# Galka.net
KiCad netlist of a schematic drawn in EAGLE
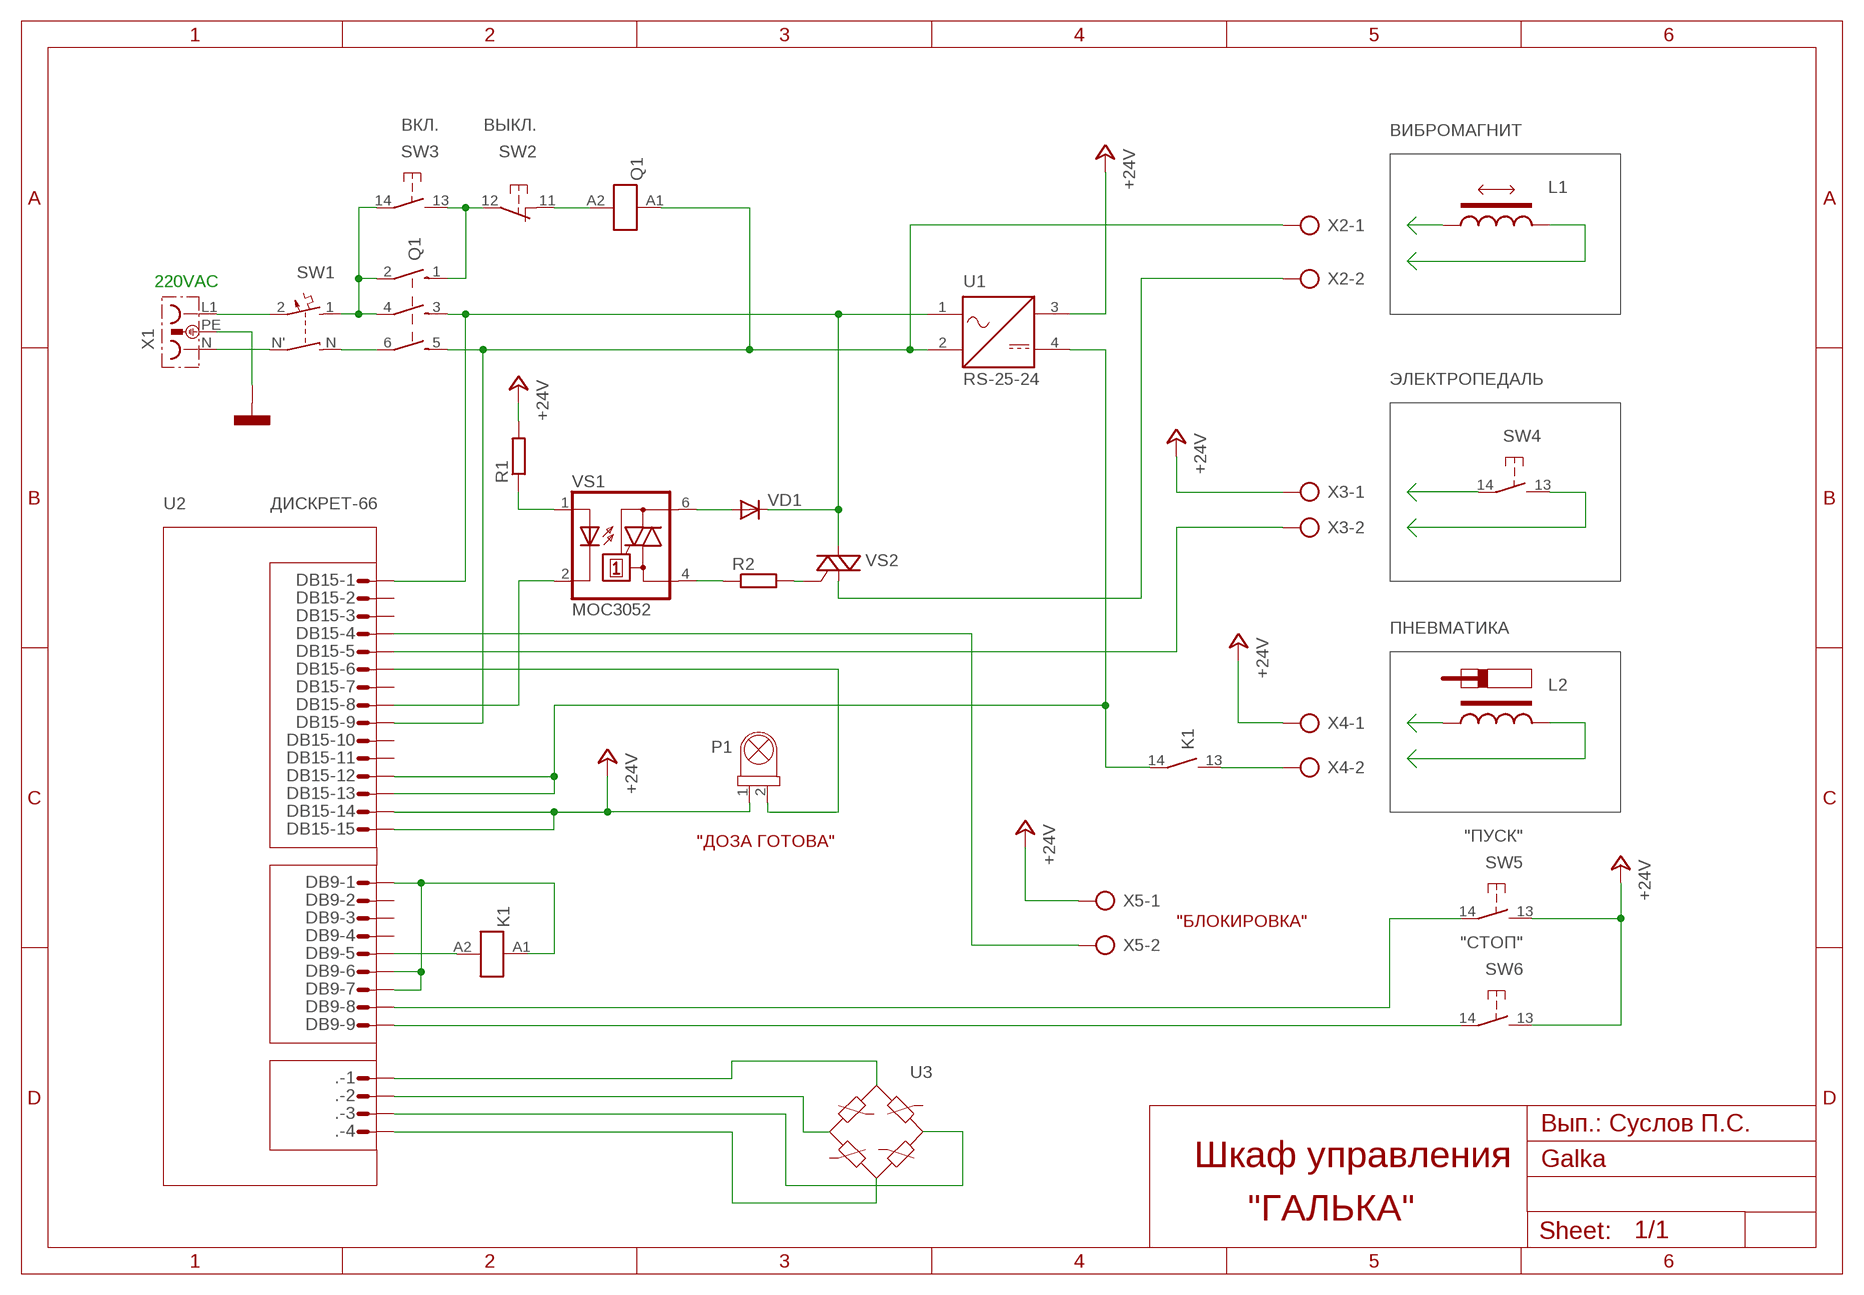
[diagram p0: schematic, sheet 1]

(export (version "E")
  (design (tool "Eeschema 10.0.6"))
  (components
    (comp (ref ".")
      (value "L04P")
      (footprint "eagle-import:L04P")
      (libsource (lib "eagle-import") (part "L04P"))
    )
    (comp (ref "DB9")
      (value "L09P")
      (footprint "eagle-import:L09P")
      (libsource (lib "eagle-import") (part "L09P"))
    )
    (comp (ref "DB15")
      (value "L15P")
      (footprint "eagle-import:L15P")
      (libsource (lib "eagle-import") (part "L15P"))
    )
    (comp (ref "K1")
      (value "HILFSSCHUETZ_13-14")
      (footprint "eagle-import:HILFSSCHUETZ_13-14")
      (libsource (lib "eagle-import") (part "HILFSSCHUETZ_13-14"))
    )
    (comp (ref "L1")
      (value "L-US0204/5")
      (footprint "eagle-import:0204_5")
      (libsource (lib "eagle-import") (part "L-US0204/5"))
    )
    (comp (ref "L2")
      (value "L-US0204/5")
      (footprint "eagle-import:0204_5")
      (libsource (lib "eagle-import") (part "L-US0204/5"))
    )
    (comp (ref "P1")
      (value "BLINK/BLITZLEUCHTE")
      (footprint "eagle-import:LAMPE")
      (libsource (lib "eagle-import") (part "BLINK/BLITZLEUCHTE"))
    )
    (comp (ref "Q1")
      (value "HAUPTSCHUETZ_3-POL")
      (footprint "eagle-import:HAUPTSCHUETZ_3-POL")
      (libsource (lib "eagle-import") (part "HAUPTSCHUETZ_3-POL"))
    )
    (comp (ref "R1")
      (value "R-EU_0204/2V")
      (footprint "eagle-import:0204V")
      (libsource (lib "eagle-import") (part "R-EU_0204/2V"))
    )
    (comp (ref "R2")
      (value "R-EU_0204/2V")
      (footprint "eagle-import:0204V")
      (libsource (lib "eagle-import") (part "R-EU_0204/2V"))
    )
    (comp (ref "SW1")
      (value "LEITUNGSSCHUTZSCHALTER_2-POL")
      (footprint "eagle-import:LEITUNGSSCHUTZSCHALTER_2-POL")
      (libsource (lib "eagle-import") (part "LEITUNGSSCHUTZSCHALTER_2-POL"))
    )
    (comp (ref "SW2")
      (value "ВЫКЛ.")
      (footprint "eagle-import:OEFFNER_TASTSCHALTER")
      (libsource (lib "eagle-import") (part "OEFFNER_TASTSCHALTER"))
    )
    (comp (ref "SW3")
      (value "ВКЛ.")
      (footprint "eagle-import:SCHLIESSER_TASTSCHALTER")
      (libsource (lib "eagle-import") (part "SCHLIESSER_TASTSCHALTER"))
    )
    (comp (ref "SW4")
      (value "SCHLIESSER_TASTSCHALTER")
      (footprint "eagle-import:SCHLIESSER_TASTSCHALTER")
      (libsource (lib "eagle-import") (part "SCHLIESSER_TASTSCHALTER"))
    )
    (comp (ref "SW5")
      (value "\"ПУСК\"")
      (footprint "eagle-import:SCHLIESSER_TASTSCHALTER")
      (libsource (lib "eagle-import") (part "SCHLIESSER_TASTSCHALTER"))
    )
    (comp (ref "SW6")
      (value "\"СТОП\"")
      (footprint "eagle-import:SCHLIESSER_TASTSCHALTER")
      (libsource (lib "eagle-import") (part "SCHLIESSER_TASTSCHALTER"))
    )
    (comp (ref "U1")
      (value "RS-25-24")
      (footprint "eagle-import:NETZTEIL_GLEICHSPANNUNG")
      (libsource (lib "eagle-import") (part "NETZTEIL_GLEICHSPANNUNG"))
    )
    (comp (ref "VD1")
      (value "1N4148DO35-7")
      (footprint "eagle-import:DO35-7")
      (libsource (lib "eagle-import") (part "1N4148DO35-7"))
    )
    (comp (ref "VS1")
      (value "MOC3052")
      (footprint "eagle-import:DIL06B")
      (libsource (lib "eagle-import") (part "MOC30T42"))
    )
    (comp (ref "VS2")
      (value "TRIAC")
      (footprint "eagle-import:TRIAC")
      (libsource (lib "eagle-import") (part "TRIAC"))
    )
    (comp (ref "X1")
      (value "STECKDOSE")
      (footprint "eagle-import:STECKDOSE")
      (libsource (lib "eagle-import") (part "STECKDOSE"))
    )
    (comp (ref "X2")
      (value "AK500/2")
      (footprint "eagle-import:AK500_2")
      (libsource (lib "eagle-import") (part "AK500/2"))
    )
    (comp (ref "X3")
      (value "AK500/2")
      (footprint "eagle-import:AK500_2")
      (libsource (lib "eagle-import") (part "AK500/2"))
    )
    (comp (ref "X4")
      (value "AK500/2")
      (footprint "eagle-import:AK500_2")
      (libsource (lib "eagle-import") (part "AK500/2"))
    )
    (comp (ref "X5")
      (value "AK500/2")
      (footprint "eagle-import:AK500_2")
      (libsource (lib "eagle-import") (part "AK500/2"))
    )
    (comp (ref "X6")
      (value "MASSE_ALLGEMEIN")
      (footprint "eagle-import:MASSE_ALLGEMEIN")
      (libsource (lib "eagle-import") (part "MASSE_ALLGEMEIN"))
    )
  )
  (nets
    (net (code "1") (name "+24V") (class "Default")
      (node (ref "DB15") (pin "14") (pinfunction "S_14") (pintype "passive"))
      (node (ref "DB15") (pin "15") (pinfunction "S_15") (pintype "passive"))
      (node (ref "P1") (pin "1") (pinfunction "X1_1") (pintype "passive"))
      (node (ref "R1") (pin "2") (pinfunction "2_2") (pintype "passive"))
      (node (ref "SW5") (pin "13") (pinfunction "3_13") (pintype "input"))
      (node (ref "SW6") (pin "13") (pinfunction "3_13") (pintype "input"))
      (node (ref "U1") (pin "3") (pinfunction "3_3") (pintype "passive"))
      (node (ref "X3") (pin "1") (pinfunction "KL_1") (pintype "passive"))
      (node (ref "X4") (pin "1") (pinfunction "KL_1") (pintype "passive"))
      (node (ref "X5") (pin "1") (pinfunction "KL_1") (pintype "passive"))
    )
    (net (code "2") (name "/SW1") (class "Default")
      (node (ref "DB15") (pin "1") (pinfunction "S_1") (pintype "passive"))
      (node (ref "Q1") (pin "3") (pinfunction "3_3") (pintype "passive"))
      (node (ref "SW1") (pin "2") (pinfunction "2_2") (pintype "passive"))
      (node (ref "U1") (pin "1") (pinfunction "1_1") (pintype "passive"))
      (node (ref "VD1") (pin "C") (pinfunction "C_C") (pintype "passive"))
      (node (ref "VS2") (pin "A1") (pinfunction "A1_A1") (pintype "passive"))
      (node (ref "X1") (pin "L1") (pinfunction "L1_L1") (pintype "passive"))
    )
    (net (code "3") (name "Net-(DB9A-S)") (class "Default")
      (node (ref "DB9") (pin "1") (pinfunction "S_1") (pintype "passive"))
      (node (ref "DB9") (pin "6") (pinfunction "S_6") (pintype "passive"))
      (node (ref "DB9") (pin "7") (pinfunction "S_7") (pintype "passive"))
      (node (ref "K1") (pin "A1") (pinfunction "A1_A1") (pintype "input"))
    )
    (net (code "4") (name "Net-(DB9E-S)") (class "Default")
      (node (ref "DB9") (pin "5") (pinfunction "S_5") (pintype "passive"))
      (node (ref "K1") (pin "A2") (pinfunction "A2_A2") (pintype "input"))
    )
    (net (code "5") (name "Net-(DB9H-S)") (class "Default")
      (node (ref "DB9") (pin "8") (pinfunction "S_8") (pintype "passive"))
      (node (ref "SW5") (pin "14") (pinfunction "4_14") (pintype "input"))
    )
    (net (code "6") (name "Net-(DB9I-S)") (class "Default")
      (node (ref "DB9") (pin "9") (pinfunction "S_9") (pintype "passive"))
      (node (ref "SW6") (pin "14") (pinfunction "4_14") (pintype "input"))
    )
    (net (code "7") (name "Net-(DB15D-S)") (class "Default")
      (node (ref "DB15") (pin "12") (pinfunction "S_12") (pintype "passive"))
      (node (ref "DB15") (pin "13") (pinfunction "S_13") (pintype "passive"))
      (node (ref "K1") (pin "14") (pinfunction "4_14") (pintype "passive"))
      (node (ref "U1") (pin "4") (pinfunction "4_4") (pintype "passive"))
    )
    (net (code "8") (name "Net-(DB15J-S)") (class "Default")
      (node (ref "DB15") (pin "4") (pinfunction "S_4") (pintype "passive"))
      (node (ref "X5") (pin "2") (pinfunction "KL_2") (pintype "passive"))
    )
    (net (code "9") (name "Net-(DB15K-S)") (class "Default")
      (node (ref "DB15") (pin "5") (pinfunction "S_5") (pintype "passive"))
      (node (ref "X3") (pin "2") (pinfunction "KL_2") (pintype "passive"))
    )
    (net (code "10") (name "Net-(DB15L-S)") (class "Default")
      (node (ref "DB15") (pin "6") (pinfunction "S_6") (pintype "passive"))
      (node (ref "P1") (pin "2") (pinfunction "X2_2") (pintype "passive"))
    )
    (net (code "11") (name "Net-(DB15N-S)") (class "Default")
      (node (ref "DB15") (pin "8") (pinfunction "S_8") (pintype "passive"))
      (node (ref "VS1") (pin "2") (pinfunction "C_2") (pintype "passive"))
    )
    (net (code "12") (name "Net-(DB15O-S)") (class "Default")
      (node (ref "DB15") (pin "9") (pinfunction "S_9") (pintype "passive"))
      (node (ref "Q1") (pin "5") (pinfunction "5_5") (pintype "passive"))
      (node (ref "Q1") (pin "A1") (pinfunction "A1_A1") (pintype "input"))
      (node (ref "U1") (pin "2") (pinfunction "2_2") (pintype "passive"))
      (node (ref "X2") (pin "1") (pinfunction "KL_1") (pintype "passive"))
    )
    (net (code "13") (name "Net-(K1A-3)") (class "Default")
      (node (ref "K1") (pin "13") (pinfunction "3_13") (pintype "passive"))
      (node (ref "X4") (pin "2") (pinfunction "KL_2") (pintype "passive"))
    )
    (net (code "14") (name "Net-(Q1-Pad6)") (class "Default")
      (node (ref "Q1") (pin "6") (pinfunction "6_6") (pintype "passive"))
      (node (ref "SW1") (pin "N") (pinfunction "N_N") (pintype "passive"))
    )
    (net (code "15") (name "Net-(R2-Pad2)") (class "Default")
      (node (ref "R2") (pin "2") (pinfunction "2_2") (pintype "passive"))
      (node (ref "VS2") (pin "G") (pinfunction "G_G") (pintype "passive"))
    )
    (net (code "16") (name "Net-(SW1-N-PadN')") (class "Default")
      (node (ref "SW1") (pin "N'") (pinfunction "N_N'") (pintype "passive"))
      (node (ref "X1") (pin "N") (pinfunction "N_N") (pintype "passive"))
    )
    (net (code "17") (name "Net-(SW2-1)") (class "Default")
      (node (ref "Q1") (pin "A2") (pinfunction "A2_A2") (pintype "input"))
      (node (ref "SW2") (pin "11") (pinfunction "1_11") (pintype "input"))
    )
    (net (code "18") (name "Net-(SW2-2)") (class "Default")
      (node (ref "Q1") (pin "1") (pinfunction "1_1") (pintype "passive"))
      (node (ref "SW2") (pin "12") (pinfunction "2_12") (pintype "input"))
      (node (ref "SW3") (pin "13") (pinfunction "3_13") (pintype "input"))
    )
    (net (code "19") (name "Net-(SW3-4)") (class "Default")
      (node (ref "Q1") (pin "2") (pinfunction "2_2") (pintype "passive"))
      (node (ref "Q1") (pin "4") (pinfunction "4_4") (pintype "passive"))
      (node (ref "SW1") (pin "1") (pinfunction "1_1") (pintype "passive"))
      (node (ref "SW3") (pin "14") (pinfunction "4_14") (pintype "input"))
    )
    (net (code "20") (name "Net-(VS1-A)") (class "Default")
      (node (ref "R1") (pin "1") (pinfunction "1_1") (pintype "passive"))
      (node (ref "VS1") (pin "1") (pinfunction "A_1") (pintype "passive"))
    )
    (net (code "21") (name "Net-(VS1-A1)") (class "Default")
      (node (ref "R2") (pin "1") (pinfunction "1_1") (pintype "passive"))
      (node (ref "VS1") (pin "4") (pinfunction "A1_4") (pintype "passive"))
    )
    (net (code "22") (name "Net-(VS1-A2)") (class "Default")
      (node (ref "VD1") (pin "A") (pinfunction "A_A") (pintype "passive"))
      (node (ref "VS1") (pin "6") (pinfunction "A2_6") (pintype "passive"))
    )
    (net (code "23") (name "Net-(X2B-KL)") (class "Default")
      (node (ref "VS2") (pin "A2") (pinfunction "A2_A2") (pintype "passive"))
      (node (ref "X2") (pin "2") (pinfunction "KL_2") (pintype "passive"))
    )
    (net (code "24") (name "Net-(X6-0V)") (class "Default")
      (node (ref "X1") (pin "PE") (pinfunction "PE_PE") (pintype "passive"))
      (node (ref "X6") (pin "1") (pinfunction "0V_1") (pintype "passive"))
    )
    (net (code "25") (name "unconnected-(.A-S-Pad1)") (class "Default")
      (node (ref ".") (pin "1") (pinfunction "S_1") (pintype "passive"))
    )
    (net (code "26") (name "unconnected-(.B-S-Pad2)") (class "Default")
      (node (ref ".") (pin "2") (pinfunction "S_2") (pintype "passive"))
    )
    (net (code "27") (name "unconnected-(.C-S-Pad3)") (class "Default")
      (node (ref ".") (pin "3") (pinfunction "S_3") (pintype "passive"))
    )
    (net (code "28") (name "unconnected-(.D-S-Pad4)") (class "Default")
      (node (ref ".") (pin "4") (pinfunction "S_4") (pintype "passive"))
    )
    (net (code "29") (name "unconnected-(DB9B-S-Pad2)") (class "Default")
      (node (ref "DB9") (pin "2") (pinfunction "S_2") (pintype "passive"))
    )
    (net (code "30") (name "unconnected-(DB9C-S-Pad3)") (class "Default")
      (node (ref "DB9") (pin "3") (pinfunction "S_3") (pintype "passive"))
    )
    (net (code "31") (name "unconnected-(DB9D-S-Pad4)") (class "Default")
      (node (ref "DB9") (pin "4") (pinfunction "S_4") (pintype "passive"))
    )
    (net (code "32") (name "unconnected-(DB15B-S-Pad10)") (class "Default")
      (node (ref "DB15") (pin "10") (pinfunction "S_10") (pintype "passive"))
    )
    (net (code "33") (name "unconnected-(DB15C-S-Pad11)") (class "Default")
      (node (ref "DB15") (pin "11") (pinfunction "S_11") (pintype "passive"))
    )
    (net (code "34") (name "unconnected-(DB15H-S-Pad2)") (class "Default")
      (node (ref "DB15") (pin "2") (pinfunction "S_2") (pintype "passive"))
    )
    (net (code "35") (name "unconnected-(DB15I-S-Pad3)") (class "Default")
      (node (ref "DB15") (pin "3") (pinfunction "S_3") (pintype "passive"))
    )
    (net (code "36") (name "unconnected-(DB15M-S-Pad7)") (class "Default")
      (node (ref "DB15") (pin "7") (pinfunction "S_7") (pintype "passive"))
    )
    (net (code "37") (name "unconnected-(L1-Pad1)") (class "Default")
      (node (ref "L1") (pin "1") (pinfunction "1_1") (pintype "passive"))
    )
    (net (code "38") (name "unconnected-(L1-Pad2)") (class "Default")
      (node (ref "L1") (pin "2") (pinfunction "2_2") (pintype "passive"))
    )
    (net (code "39") (name "unconnected-(L2-Pad1)") (class "Default")
      (node (ref "L2") (pin "1") (pinfunction "1_1") (pintype "passive"))
    )
    (net (code "40") (name "unconnected-(L2-Pad2)") (class "Default")
      (node (ref "L2") (pin "2") (pinfunction "2_2") (pintype "passive"))
    )
    (net (code "41") (name "unconnected-(SW4-3-Pad13)") (class "Default")
      (node (ref "SW4") (pin "13") (pinfunction "3_13") (pintype "input"))
    )
    (net (code "42") (name "unconnected-(SW4-4-Pad14)") (class "Default")
      (node (ref "SW4") (pin "14") (pinfunction "4_14") (pintype "input"))
    )
  )
)
